# Acoustics_Connections_RP2040.net
KiCad netlist of a schematic drawn in Altium Designer
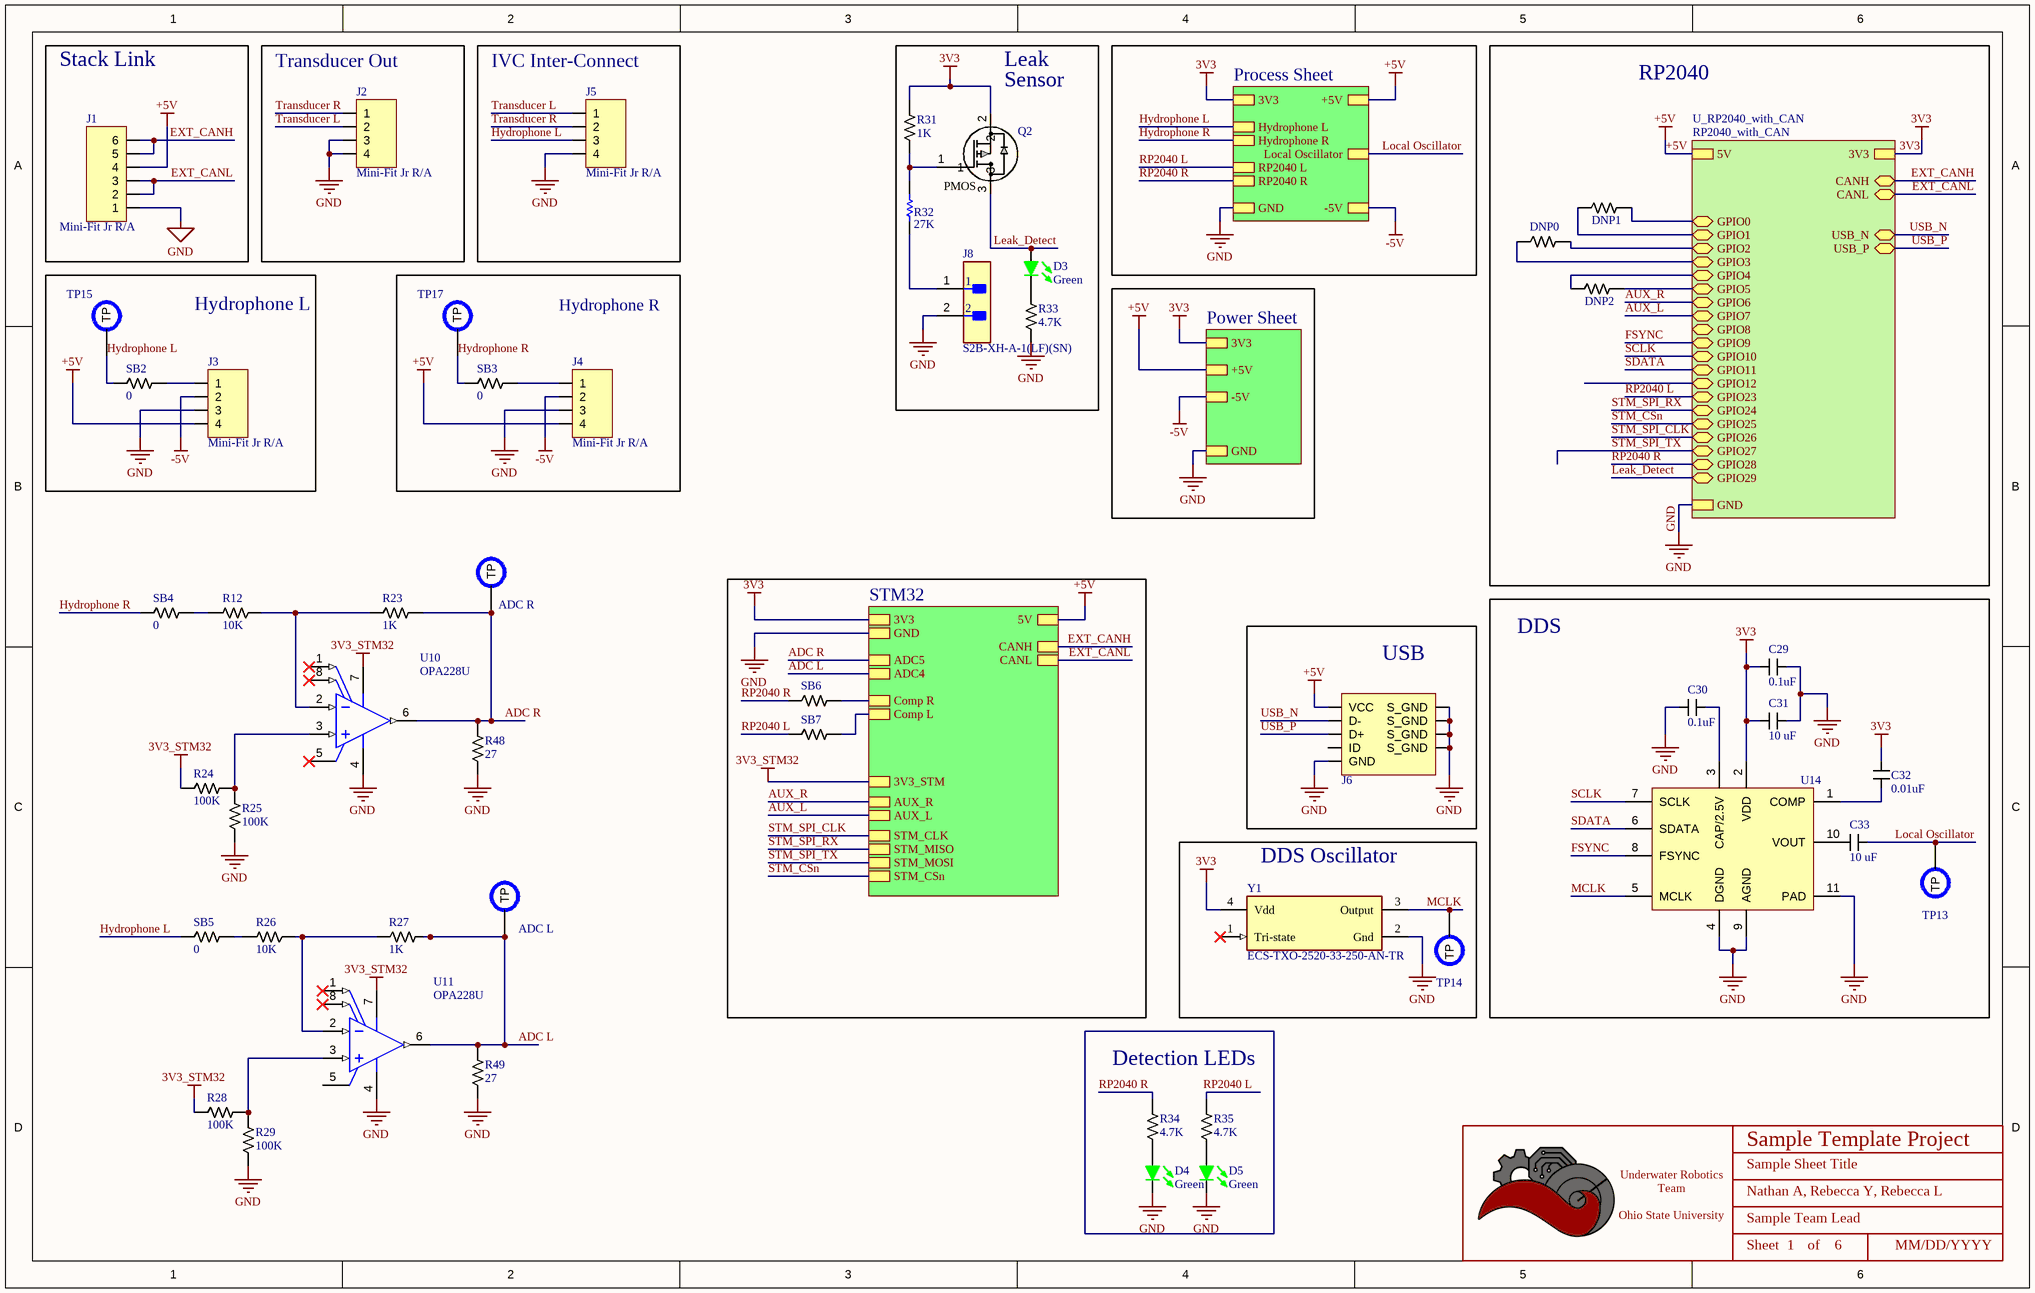
[diagram p0: [Acoustics] Connections & RP2040.SchDoc]

(export (version "E")
  (design (tool "Eeschema 10.0.6"))
  (components
    (comp (ref "ADC L")
      (value "PCB Test Point")
      (footprint "TESTPOINT_1.2MM")
      (fields (field (name "MADE BY") "Robert Pafford"))
      (libsource (lib "Connectors") (part "TESTPOINT"))
    )
    (comp (ref "ADC R")
      (value "PCB Test Point")
      (footprint "TESTPOINT_1.2MM")
      (fields (field (name "MADE BY") "Robert Pafford"))
      (libsource (lib "Connectors") (part "TESTPOINT"))
    )
    (comp (ref "C29")
      (value "0.1uF")
      (footprint "CAPACITOR_0603")
      (description "Cap 100nF 6.3V +/-10%\r\nCeramic 0603")
      (fields
        (field (name "TOLERANCE") "+/- 10%")
        (field (name "VOLTAGE") "6.3V")
        (field (name "MADE BY") "Flip B")
      )
      (libsource (lib "Capacitors") (part "CAPACITOR_0.1uF_0603"))
    )
    (comp (ref "C30")
      (value "0.1uF")
      (footprint "CAPACITOR_0603")
      (description "Cap 100nF 6.3V +/-10%\r\nCeramic 0603")
      (fields
        (field (name "TOLERANCE") "+/- 10%")
        (field (name "VOLTAGE") "6.3V")
        (field (name "MADE BY") "Flip B")
      )
      (libsource (lib "Capacitors") (part "CAPACITOR_0.1uF_0603"))
    )
    (comp (ref "C31")
      (value "10uF Ceramic 6.3V")
      (footprint "CAPACITOR_0603")
      (description "Cap 10uF 6.3V +/-20%\r\nCeramic 0603")
      (fields
        (field (name "TOLERANCE") "+/- 20%")
        (field (name "VOLTAGE") "6.3V")
        (field (name "VALUE (UF)") "10 uF")
        (field (name "MADE BY") "Flip B")
      )
      (libsource (lib "Capacitors") (part "CAPACITOR_10uF_0603"))
    )
    (comp (ref "C32")
      (value "0.01uF")
      (footprint "CAPACITOR_0603")
      (description "10000 pF ±10% 50V Ceramic Capacitor X7R 0603 (1608 Metric)")
      (fields
        (field (name "TOLERANCE") "+/- 10%")
        (field (name "VOLTAGE") "6.3V")
        (field (name "MADE BY") "Flip B")
      )
      (libsource (lib "Capacitors") (part "CAPACITOR_0.01uF_0603_50V"))
    )
    (comp (ref "C33")
      (value "10uF Ceramic 6.3V")
      (footprint "CAPACITOR_0603")
      (description "Cap 10uF 6.3V +/-20%\r\nCeramic 0603")
      (fields
        (field (name "TOLERANCE") "+/- 20%")
        (field (name "VOLTAGE") "6.3V")
        (field (name "VALUE (UF)") "10 uF")
        (field (name "MADE BY") "Flip B")
      )
      (libsource (lib "Capacitors") (part "CAPACITOR_10uF_0603"))
    )
    (comp (ref "D3")
      (value "IN-S63AT5G")
      (footprint "LED_0603")
      (description "LED Green Vf= 3V If = 0.005A\r\nIN-S63AT5G")
      (fields (field (name "COLOR") "Green") (field (name "MADE BY") "Robert Pafford"))
      (libsource (lib "Diodes") (part "LED_Green_0603_3V"))
    )
    (comp (ref "D4")
      (value "IN-S63AT5G")
      (footprint "LED_0603")
      (description "LED Green Vf= 3V If = 0.005A\r\nIN-S63AT5G")
      (fields (field (name "COLOR") "Green") (field (name "MADE BY") "Robert Pafford"))
      (libsource (lib "Diodes") (part "LED_Green_0603_3V"))
    )
    (comp (ref "D5")
      (value "IN-S63AT5G")
      (footprint "LED_0603")
      (description "LED Green Vf= 3V If = 0.005A\r\nIN-S63AT5G")
      (fields (field (name "COLOR") "Green") (field (name "MADE BY") "Robert Pafford"))
      (libsource (lib "Diodes") (part "LED_Green_0603_3V"))
    )
    (comp (ref "DNP0")
      (value "DNP")
      (footprint "RESISTOR_0402")
      (description "Do Not Populate 0402")
      (libsource (lib "Resistors") (part "DNP_0402"))
    )
    (comp (ref "DNP1")
      (value "DNP")
      (footprint "RESISTOR_0402")
      (description "Do Not Populate 0402")
      (libsource (lib "Resistors") (part "DNP_0402"))
    )
    (comp (ref "DNP2")
      (value "DNP")
      (footprint "RESISTOR_0402")
      (description "Do Not Populate 0402")
      (libsource (lib "Resistors") (part "DNP_0402"))
    )
    (comp (ref "J1")
      (value "Mini-Fit Jr R/A")
      (footprint "CONN_MOLEX_MINIFIT JR_6 POS_R/A")
      (description "Molex Minifit Jr. 5569 \r\n6 Pos R/A Natural")
      (fields (field (name "MANUFACTURER") "Molex") (field (name "CREATED BY") "Flip B"))
      (libsource (lib "Connectors") (part "CONN_MOLEX_MINIFIT JR_6POS_R/A"))
    )
    (comp (ref "J2")
      (value "Mini-Fit Jr R/A")
      (footprint "CONN_MOLEX_MINIFIT JR_4 POS_R/A")
      (description "Molex Minifit Jr. 5569 \r\n4 Pos R/A Natural")
      (fields (field (name "MANUFACTURER") "Molex") (field (name "CREATED BY") "Flip B"))
      (libsource (lib "Connectors") (part "CONN_MOLEX_MINIFIT JR_4POS_R/A"))
    )
    (comp (ref "J3")
      (value "Mini-Fit Jr R/A")
      (footprint "CONN_MOLEX_MINIFIT JR_4 POS_R/A")
      (description "Molex Minifit Jr. 5569 \r\n4 Pos R/A Natural")
      (fields (field (name "MANUFACTURER") "Molex") (field (name "CREATED BY") "Flip B"))
      (libsource (lib "Connectors") (part "CONN_MOLEX_MINIFIT JR_4POS_R/A"))
    )
    (comp (ref "J4")
      (value "Mini-Fit Jr R/A")
      (footprint "CONN_MOLEX_MINIFIT JR_4 POS_R/A")
      (description "Molex Minifit Jr. 5569 \r\n4 Pos R/A Natural")
      (fields (field (name "MANUFACTURER") "Molex") (field (name "CREATED BY") "Flip B"))
      (libsource (lib "Connectors") (part "CONN_MOLEX_MINIFIT JR_4POS_R/A"))
    )
    (comp (ref "J5")
      (value "Mini-Fit Jr R/A")
      (footprint "CONN_MOLEX_MINIFIT JR_4 POS_R/A")
      (description "Molex Minifit Jr. 5569 \r\n4 Pos R/A Natural")
      (fields (field (name "MANUFACTURER") "Molex") (field (name "CREATED BY") "Flip B"))
      (libsource (lib "Connectors") (part "CONN_MOLEX_MINIFIT JR_4POS_R/A"))
    )
    (comp (ref "J6")
      (value "USB_MICRO R/A")
      (footprint "CONN_MINIUSB")
      (description "Amphenol Micro USB-B\r\nUSB2.0 5 Pin Right Angle SMD")
      (fields (field (name "MANUFACTURER") "Amphenol") (field (name "CREATED BY") "Flip B"))
      (libsource (lib "Connectors") (part "CONN_MICROUSB"))
    )
    (comp (ref "J8")
      (value "S2B-XH-A-1(LF)(SN)")
      (footprint "FP-S2B-XH-A-1_LF_SN-MFG")
      (description "CONN HEADER R/A 2POS 2.5MM")
      (libsource (lib "Altium Content Vault") (part "3bc925449376181038e59eaffc5286c"))
    )
    (comp (ref "Q2")
      (value "MOSFET P-CHANNEL 20V 4.7A SOT23")
      (footprint "SOT-23-3")
      (description "P-Channel 20 V 4.7A (Tc) 1.56W (Tc) Surface Mount SOT-23")
      (fields
        (field (name "MANUFACTURER_PART_NUMBER") "TSM500P02CX")
        (field (name "CREATED BY") "Robert Pafford")
      )
      (libsource (lib "Transistors") (part "TSM500P02CX"))
    )
    (comp (ref "R12")
      (value "10k Ohm 5% 1/10W")
      (footprint "RESISTOR_0603")
      (description "RES 10k OHM 5% 1/10W 0603")
      (fields
        (field (name "TOLERANCE") "+/- 5%")
        (field (name "VALUE  (OHMS)") "10K")
        (field (name "MADE BY") "Robert Pafford")
      )
      (libsource (lib "Resistors") (part "RESISTOR_10K_0603"))
    )
    (comp (ref "R23")
      (value "1k Ohm 5% 1/8W")
      (footprint "RESISTOR_0603")
      (description "RES 1k OHM 5% 1/8W 0603")
      (fields
        (field (name "TOLERANCE") "+/- 5%")
        (field (name "VALUE  (OHMS)") "1K")
        (field (name "MADE BY") "Robert Pafford")
      )
      (libsource (lib "Resistors") (part "RESISTOR_1K_0603"))
    )
    (comp (ref "R24")
      (value "100k Ohm 5% 1/8W")
      (footprint "RESISTOR_0603")
      (description "RES 100k OHM 5% 1/10W 0603")
      (fields
        (field (name "TOLERANCE") "+/- 5%")
        (field (name "VALUE  (OHMS)") "100K")
        (field (name "MADE BY") "Flip B")
      )
      (libsource (lib "Resistors") (part "RESISTOR_100K_0603"))
    )
    (comp (ref "R25")
      (value "100k Ohm 5% 1/8W")
      (footprint "RESISTOR_0603")
      (description "RES 100k OHM 5% 1/10W 0603")
      (fields
        (field (name "TOLERANCE") "+/- 5%")
        (field (name "VALUE  (OHMS)") "100K")
        (field (name "MADE BY") "Flip B")
      )
      (libsource (lib "Resistors") (part "RESISTOR_100K_0603"))
    )
    (comp (ref "R26")
      (value "10k Ohm 5% 1/10W")
      (footprint "RESISTOR_0603")
      (description "RES 10k OHM 5% 1/10W 0603")
      (fields
        (field (name "TOLERANCE") "+/- 5%")
        (field (name "VALUE  (OHMS)") "10K")
        (field (name "MADE BY") "Robert Pafford")
      )
      (libsource (lib "Resistors") (part "RESISTOR_10K_0603"))
    )
    (comp (ref "R27")
      (value "1k Ohm 5% 1/8W")
      (footprint "RESISTOR_0603")
      (description "RES 1k OHM 5% 1/8W 0603")
      (fields
        (field (name "TOLERANCE") "+/- 5%")
        (field (name "VALUE  (OHMS)") "1K")
        (field (name "MADE BY") "Robert Pafford")
      )
      (libsource (lib "Resistors") (part "RESISTOR_1K_0603"))
    )
    (comp (ref "R28")
      (value "100k Ohm 5% 1/8W")
      (footprint "RESISTOR_0603")
      (description "RES 100k OHM 5% 1/10W 0603")
      (fields
        (field (name "TOLERANCE") "+/- 5%")
        (field (name "VALUE  (OHMS)") "100K")
        (field (name "MADE BY") "Flip B")
      )
      (libsource (lib "Resistors") (part "RESISTOR_100K_0603"))
    )
    (comp (ref "R29")
      (value "100k Ohm 5% 1/8W")
      (footprint "RESISTOR_0603")
      (description "RES 100k OHM 5% 1/10W 0603")
      (fields
        (field (name "TOLERANCE") "+/- 5%")
        (field (name "VALUE  (OHMS)") "100K")
        (field (name "MADE BY") "Flip B")
      )
      (libsource (lib "Resistors") (part "RESISTOR_100K_0603"))
    )
    (comp (ref "R31")
      (value "1k Ohm 1% 1/16W")
      (footprint "RESISTOR_0402")
      (description "RES 1k OHM 1% 1/16W 0402")
      (fields
        (field (name "TOLERANCE") "+/- 1%")
        (field (name "VALUE  (OHMS)") "1K")
        (field (name "MADE BY") "Robert Pafford")
      )
      (libsource (lib "Resistors") (part "RESISTOR_1K_0402"))
    )
    (comp (ref "R32")
      (value "27K")
      (footprint "RESC1005X40X25ML05T05")
      (description "RES SMD 27K OHM 5% 1/10W 0402ERJ-2GEJ273X")
      (fields (field (name "MANUFACTURER") "Panasonic") (field (name "PART NUMBER") "ERJ-2GEJ273X"))
      (libsource (lib "Altium Content Vault") (part "RES"))
    )
    (comp (ref "R33")
      (value "4.7k Ohm 5% 1/10W")
      (footprint "RESISTOR_0603")
      (description "RES 4.7k OHM 5% 1/10W 0603")
      (fields
        (field (name "TOLERANCE") "+/- 5%")
        (field (name "VALUE  (OHMS)") "4.7K")
        (field (name "MADE BY") "Robert Pafford")
      )
      (libsource (lib "Resistors") (part "RESISTOR_4.7K_0603"))
    )
    (comp (ref "R34")
      (value "4.7k Ohm 5% 1/10W")
      (footprint "RESISTOR_0603")
      (description "RES 4.7k OHM 5% 1/10W 0603")
      (fields
        (field (name "TOLERANCE") "+/- 5%")
        (field (name "VALUE  (OHMS)") "4.7K")
        (field (name "MADE BY") "Robert Pafford")
      )
      (libsource (lib "Resistors") (part "RESISTOR_4.7K_0603"))
    )
    (comp (ref "R35")
      (value "4.7k Ohm 5% 1/10W")
      (footprint "RESISTOR_0603")
      (description "RES 4.7k OHM 5% 1/10W 0603")
      (fields
        (field (name "TOLERANCE") "+/- 5%")
        (field (name "VALUE  (OHMS)") "4.7K")
        (field (name "MADE BY") "Robert Pafford")
      )
      (libsource (lib "Resistors") (part "RESISTOR_4.7K_0603"))
    )
    (comp (ref "R48")
      (value "27 Ohm 5% 1/8W")
      (footprint "RESISTOR_0603")
      (description "RES 27 OHM 5% 1/8W 0603")
      (fields
        (field (name "TOLERANCE") "+/- 5%")
        (field (name "VALUE  (OHMS)") "27")
        (field (name "MADE BY") "Robert Pafford")
      )
      (libsource (lib "Resistors") (part "RESISTOR_27_0603"))
    )
    (comp (ref "R49")
      (value "27 Ohm 5% 1/8W")
      (footprint "RESISTOR_0603")
      (description "RES 27 OHM 5% 1/8W 0603")
      (fields
        (field (name "TOLERANCE") "+/- 5%")
        (field (name "VALUE  (OHMS)") "27")
        (field (name "MADE BY") "Robert Pafford")
      )
      (libsource (lib "Resistors") (part "RESISTOR_27_0603"))
    )
    (comp (ref "SB2")
      (value "0 Ohm Jumper No Fit")
      (footprint "RESISTOR_0603")
      (description "0 Ohm Jumper No Fit for Solder Bridge")
      (fields (field (name "VALUE  (OHMS)") "0") (field (name "MADE BY") "Robert Pafford"))
      (libsource (lib "Resistors") (part "JUMPER_0_0603"))
    )
    (comp (ref "SB3")
      (value "0 Ohm Jumper No Fit")
      (footprint "RESISTOR_0603")
      (description "0 Ohm Jumper No Fit for Solder Bridge")
      (fields (field (name "VALUE  (OHMS)") "0") (field (name "MADE BY") "Robert Pafford"))
      (libsource (lib "Resistors") (part "JUMPER_0_0603"))
    )
    (comp (ref "SB4")
      (value "0 Ohm Jumper No Fit")
      (footprint "RESISTOR_0603")
      (description "0 Ohm Jumper No Fit for Solder Bridge")
      (fields (field (name "VALUE  (OHMS)") "0") (field (name "MADE BY") "Robert Pafford"))
      (libsource (lib "Resistors") (part "JUMPER_0_0603"))
    )
    (comp (ref "SB5")
      (value "0 Ohm Jumper No Fit")
      (footprint "RESISTOR_0603")
      (description "0 Ohm Jumper No Fit for Solder Bridge")
      (fields (field (name "VALUE  (OHMS)") "0") (field (name "MADE BY") "Robert Pafford"))
      (libsource (lib "Resistors") (part "JUMPER_0_0603"))
    )
    (comp (ref "SB6")
      (value "0 Ohm Jumper No Fit")
      (footprint "RESISTOR_0603")
      (description "0 Ohm Jumper No Fit for Solder Bridge")
      (fields (field (name "MADE BY") "Robert Pafford"))
      (libsource (lib "Resistors") (part "JUMPER_0_0603"))
    )
    (comp (ref "SB7")
      (value "0 Ohm Jumper No Fit")
      (footprint "RESISTOR_0603")
      (description "0 Ohm Jumper No Fit for Solder Bridge")
      (fields (field (name "MADE BY") "Robert Pafford"))
      (libsource (lib "Resistors") (part "JUMPER_0_0603"))
    )
    (comp (ref "TP13")
      (value "PCB Test Point")
      (footprint "TESTPOINT_1.2MM")
      (fields (field (name "MADE BY") "Robert Pafford"))
      (libsource (lib "Connectors") (part "TESTPOINT"))
    )
    (comp (ref "TP14")
      (value "PCB Test Point")
      (footprint "TESTPOINT_1.2MM")
      (fields (field (name "MADE BY") "Robert Pafford"))
      (libsource (lib "Connectors") (part "TESTPOINT"))
    )
    (comp (ref "TP15")
      (value "PCB Test Point")
      (footprint "TESTPOINT_1.2MM")
      (fields (field (name "MADE BY") "Robert Pafford"))
      (libsource (lib "Connectors") (part "TESTPOINT"))
    )
    (comp (ref "TP17")
      (value "PCB Test Point")
      (footprint "TESTPOINT_1.2MM")
      (fields (field (name "MADE BY") "Robert Pafford"))
      (libsource (lib "Connectors") (part "TESTPOINT"))
    )
    (comp (ref "U10")
      (value "OPA228U")
      (footprint "D0008A_M")
      (fields (field (name "MANUFACTURER") "Texas Instruments"))
      (libsource (lib "Altium Content Vault") (part "TI-OPA228-X8"))
    )
    (comp (ref "U11")
      (value "OPA228U")
      (footprint "D0008A_M")
      (fields (field (name "MANUFACTURER") "Texas Instruments"))
      (libsource (lib "Altium Content Vault") (part "TI-OPA228-X8"))
    )
    (comp (ref "U14")
      (value "IC DDS 5MHZ 10BIT 10LFCSP")
      (footprint "CP-10-9")
      (description "Direct Digital Synthesis IC 10 b 5 MHz 28 b Tuning 10-LFCSP-WD (3x3)")
      (libsource (lib "Integrated Circuits") (part "AD9837ACPZ"))
    )
    (comp (ref "Y1")
      (value "ECS-TXO-2520-33-250-AN-TR")
      (footprint "FP-ECS-TXO-2520-MFG")
      (description "XTAL OSC TCXO 25.0000MHZ HCMOS")
      (libsource (lib "Altium Content Vault") (part "04cd953f3cf158082f8c09fbdb924ef"))
    )
  )
  (nets
    (net (code "1") (name "+5V") (class "Default")
      (node (ref "J1") (pin "4") (pinfunction "4_4") (pintype "passive"))
      (node (ref "J3") (pin "4") (pinfunction "4_4") (pintype "passive"))
      (node (ref "J4") (pin "4") (pinfunction "4_4") (pintype "passive"))
      (node (ref "J6") (pin "1") (pinfunction "VCC_1") (pintype "passive"))
    )
    (net (code "2") (name "-5V") (class "Default")
      (node (ref "J3") (pin "2") (pinfunction "2_2") (pintype "passive"))
      (node (ref "J4") (pin "2") (pinfunction "2_2") (pintype "passive"))
    )
    (net (code "3") (name "/ADC L") (class "Default")
      (node (ref "ADC L") (pin "TP") (pinfunction "TP_TP") (pintype "passive"))
      (node (ref "R27") (pin "1") (pinfunction "1_1") (pintype "passive"))
      (node (ref "R49") (pin "1") (pinfunction "1_1") (pintype "passive"))
      (node (ref "U11") (pin "6") (pinfunction "OUT_6") (pintype "output"))
    )
    (net (code "4") (name "/ADC R") (class "Default")
      (node (ref "ADC R") (pin "TP") (pinfunction "TP_TP") (pintype "passive"))
      (node (ref "R23") (pin "1") (pinfunction "1_1") (pintype "passive"))
      (node (ref "R48") (pin "1") (pinfunction "1_1") (pintype "passive"))
      (node (ref "U10") (pin "6") (pinfunction "OUT_6") (pintype "output"))
    )
    (net (code "7") (name "/Comp L") (class "Default")
      (node (ref "SB7") (pin "1") (pinfunction "1_1") (pintype "passive"))
    )
    (net (code "8") (name "/Comp R") (class "Default")
      (node (ref "SB6") (pin "1") (pinfunction "1_1") (pintype "passive"))
    )
    (net (code "9") (name "/EXT_CANH") (class "Default")
      (node (ref "J1") (pin "5") (pinfunction "5_5") (pintype "passive"))
      (node (ref "J1") (pin "6") (pinfunction "6_6") (pintype "passive"))
    )
    (net (code "10") (name "/EXT_CANL") (class "Default")
      (node (ref "J1") (pin "2") (pinfunction "2_2") (pintype "passive"))
      (node (ref "J1") (pin "3") (pinfunction "3_3") (pintype "passive"))
    )
    (net (code "11") (name "/FSYNC") (class "Default")
      (node (ref "U14") (pin "8") (pinfunction "FSYNC_8") (pintype "passive"))
    )
    (net (code "12") (name "/GPIO0") (class "Default")
      (node (ref "DNP1") (pin "1") (pinfunction "1_1") (pintype "passive"))
    )
    (net (code "13") (name "/GPIO1") (class "Default")
      (node (ref "DNP1") (pin "2") (pinfunction "2_2") (pintype "passive"))
    )
    (net (code "14") (name "/GPIO2") (class "Default")
      (node (ref "DNP0") (pin "1") (pinfunction "1_1") (pintype "passive"))
    )
    (net (code "15") (name "/GPIO3") (class "Default")
      (node (ref "DNP0") (pin "2") (pinfunction "2_2") (pintype "passive"))
    )
    (net (code "16") (name "/GPIO4") (class "Default")
      (node (ref "DNP2") (pin "2") (pinfunction "2_2") (pintype "passive"))
    )
    (net (code "17") (name "/GPIO5") (class "Default")
      (node (ref "DNP2") (pin "1") (pinfunction "1_1") (pintype "passive"))
    )
    (net (code "20") (name "/Hydrophone L") (class "Default")
      (node (ref "J5") (pin "3") (pinfunction "3_3") (pintype "passive"))
      (node (ref "SB2") (pin "2") (pinfunction "2_2") (pintype "passive"))
      (node (ref "SB5") (pin "2") (pinfunction "2_2") (pintype "passive"))
      (node (ref "TP15") (pin "TP") (pinfunction "TP_TP") (pintype "passive"))
    )
    (net (code "21") (name "/Hydrophone R") (class "Default")
      (node (ref "SB3") (pin "2") (pinfunction "2_2") (pintype "passive"))
      (node (ref "SB4") (pin "2") (pinfunction "2_2") (pintype "passive"))
      (node (ref "TP17") (pin "TP") (pinfunction "TP_TP") (pintype "passive"))
    )
    (net (code "22") (name "/Leak_Detect") (class "Default")
      (node (ref "D3") (pin "1") (pinfunction "1_1") (pintype "passive"))
      (node (ref "Q2") (pin "3") (pinfunction "3_3") (pintype "passive"))
    )
    (net (code "23") (name "/Local Oscillator") (class "Default")
      (node (ref "C33") (pin "2") (pinfunction "2_2") (pintype "passive"))
      (node (ref "TP13") (pin "TP") (pinfunction "TP_TP") (pintype "passive"))
    )
    (net (code "24") (name "/MCLK") (class "Default")
      (node (ref "TP14") (pin "TP") (pinfunction "TP_TP") (pintype "passive"))
      (node (ref "U14") (pin "5") (pinfunction "MCLK_5") (pintype "passive"))
      (node (ref "Y1") (pin "3") (pinfunction "Output_3") (pintype "tri_state"))
    )
    (net (code "25") (name "/RP2040 L") (class "Default")
      (node (ref "R35") (pin "1") (pinfunction "1_1") (pintype "passive"))
      (node (ref "SB7") (pin "2") (pinfunction "2_2") (pintype "passive"))
    )
    (net (code "26") (name "/RP2040 R") (class "Default")
      (node (ref "R34") (pin "1") (pinfunction "1_1") (pintype "passive"))
      (node (ref "SB6") (pin "2") (pinfunction "2_2") (pintype "passive"))
    )
    (net (code "27") (name "/SCLK") (class "Default")
      (node (ref "U14") (pin "7") (pinfunction "SCLK_7") (pintype "passive"))
    )
    (net (code "28") (name "/SDATA") (class "Default")
      (node (ref "U14") (pin "6") (pinfunction "SDATA_6") (pintype "passive"))
    )
    (net (code "33") (name "/Transducer L") (class "Default")
      (node (ref "J2") (pin "2") (pinfunction "2_2") (pintype "passive"))
      (node (ref "J5") (pin "1") (pinfunction "1_1") (pintype "passive"))
    )
    (net (code "34") (name "/Transducer R") (class "Default")
      (node (ref "J2") (pin "1") (pinfunction "1_1") (pintype "passive"))
      (node (ref "J5") (pin "2") (pinfunction "2_2") (pintype "passive"))
    )
    (net (code "35") (name "/USB_N") (class "Default")
      (node (ref "J6") (pin "2") (pinfunction "D-_2") (pintype "passive"))
    )
    (net (code "36") (name "/USB_P") (class "Default")
      (node (ref "J6") (pin "3") (pinfunction "D+_3") (pintype "passive"))
    )
    (net (code "37") (name "3V3") (class "Default")
      (node (ref "C29") (pin "2") (pinfunction "2_2") (pintype "passive"))
      (node (ref "C31") (pin "1") (pinfunction "1_1") (pintype "passive"))
      (node (ref "C32") (pin "1") (pinfunction "1_1") (pintype "passive"))
      (node (ref "Q2") (pin "2") (pinfunction "2_2") (pintype "passive"))
      (node (ref "R31") (pin "1") (pinfunction "1_1") (pintype "passive"))
      (node (ref "U14") (pin "2") (pinfunction "VDD_2") (pintype "passive"))
      (node (ref "Y1") (pin "4") (pinfunction "Vdd_4") (pintype "power_in"))
    )
    (net (code "38") (name "3V3_STM32") (class "Default")
      (node (ref "R24") (pin "2") (pinfunction "2_2") (pintype "passive"))
      (node (ref "R28") (pin "2") (pinfunction "2_2") (pintype "passive"))
      (node (ref "U10") (pin "7") (pinfunction "V+_7") (pintype "power_in"))
      (node (ref "U11") (pin "7") (pinfunction "V+_7") (pintype "power_in"))
    )
    (net (code "39") (name "GND") (class "Default")
      (node (ref "C29") (pin "1") (pinfunction "1_1") (pintype "passive"))
      (node (ref "C30") (pin "1") (pinfunction "1_1") (pintype "passive"))
      (node (ref "C31") (pin "2") (pinfunction "2_2") (pintype "passive"))
      (node (ref "D4") (pin "2") (pinfunction "2_2") (pintype "passive"))
      (node (ref "D5") (pin "2") (pinfunction "2_2") (pintype "passive"))
      (node (ref "J1") (pin "1") (pinfunction "1_1") (pintype "passive"))
      (node (ref "J2") (pin "3") (pinfunction "3_3") (pintype "passive"))
      (node (ref "J2") (pin "4") (pinfunction "4_4") (pintype "passive"))
      (node (ref "J3") (pin "3") (pinfunction "3_3") (pintype "passive"))
      (node (ref "J4") (pin "3") (pinfunction "3_3") (pintype "passive"))
      (node (ref "J5") (pin "4") (pinfunction "4_4") (pintype "passive"))
      (node (ref "J6") (pin "5") (pinfunction "GND_5") (pintype "passive"))
      (node (ref "J6") (pin "6") (pinfunction "S_GND_6") (pintype "passive"))
      (node (ref "J6") (pin "7") (pinfunction "S_GND_7") (pintype "passive"))
      (node (ref "J6") (pin "8") (pinfunction "S_GND_8") (pintype "passive"))
      (node (ref "J6") (pin "9") (pinfunction "S_GND_9") (pintype "passive"))
      (node (ref "J8") (pin "2") (pinfunction "2_2") (pintype "passive"))
      (node (ref "R25") (pin "2") (pinfunction "2_2") (pintype "passive"))
      (node (ref "R29") (pin "2") (pinfunction "2_2") (pintype "passive"))
      (node (ref "R33") (pin "2") (pinfunction "2_2") (pintype "passive"))
      (node (ref "R48") (pin "2") (pinfunction "2_2") (pintype "passive"))
      (node (ref "R49") (pin "2") (pinfunction "2_2") (pintype "passive"))
      (node (ref "U10") (pin "4") (pinfunction "V-_4") (pintype "power_in"))
      (node (ref "U11") (pin "4") (pinfunction "V-_4") (pintype "power_in"))
      (node (ref "U14") (pin "11") (pinfunction "PAD_11") (pintype "passive"))
      (node (ref "U14") (pin "4") (pinfunction "DGND_4") (pintype "passive"))
      (node (ref "U14") (pin "9") (pinfunction "AGND_9") (pintype "passive"))
      (node (ref "Y1") (pin "2") (pinfunction "Gnd_2") (pintype "power_in"))
    )
    (net (code "40") (name "Net-(D3-Pad2)") (class "Default")
      (node (ref "D3") (pin "2") (pinfunction "2_2") (pintype "passive"))
      (node (ref "R33") (pin "1") (pinfunction "1_1") (pintype "passive"))
    )
    (net (code "41") (name "Net-(D4-Pad1)") (class "Default")
      (node (ref "D4") (pin "1") (pinfunction "1_1") (pintype "passive"))
      (node (ref "R34") (pin "2") (pinfunction "2_2") (pintype "passive"))
    )
    (net (code "42") (name "Net-(D5-Pad1)") (class "Default")
      (node (ref "D5") (pin "1") (pinfunction "1_1") (pintype "passive"))
      (node (ref "R35") (pin "2") (pinfunction "2_2") (pintype "passive"))
    )
    (net (code "43") (name "Net-(J3-Pad1)") (class "Default")
      (node (ref "J3") (pin "1") (pinfunction "1_1") (pintype "passive"))
      (node (ref "SB2") (pin "1") (pinfunction "1_1") (pintype "passive"))
    )
    (net (code "44") (name "Net-(J4-Pad1)") (class "Default")
      (node (ref "J4") (pin "1") (pinfunction "1_1") (pintype "passive"))
      (node (ref "SB3") (pin "1") (pinfunction "1_1") (pintype "passive"))
    )
    (net (code "45") (name "Net-(J8-Pad1)") (class "Default")
      (node (ref "J8") (pin "1") (pinfunction "1_1") (pintype "passive"))
      (node (ref "R32") (pin "1") (pinfunction "1_1") (pintype "passive"))
    )
    (net (code "46") (name "Net-(Q2-Pad1)") (class "Default")
      (node (ref "Q2") (pin "1") (pinfunction "1_1") (pintype "passive"))
      (node (ref "R31") (pin "2") (pinfunction "2_2") (pintype "passive"))
      (node (ref "R32") (pin "2") (pinfunction "2_2") (pintype "passive"))
    )
    (net (code "47") (name "Net-(R12-Pad1)") (class "Default")
      (node (ref "R12") (pin "1") (pinfunction "1_1") (pintype "passive"))
      (node (ref "SB4") (pin "1") (pinfunction "1_1") (pintype "passive"))
    )
    (net (code "48") (name "Net-(R26-Pad1)") (class "Default")
      (node (ref "R26") (pin "1") (pinfunction "1_1") (pintype "passive"))
      (node (ref "SB5") (pin "1") (pinfunction "1_1") (pintype "passive"))
    )
    (net (code "49") (name "Net-(U10-IN+)") (class "Default")
      (node (ref "R24") (pin "1") (pinfunction "1_1") (pintype "passive"))
      (node (ref "R25") (pin "1") (pinfunction "1_1") (pintype "passive"))
      (node (ref "U10") (pin "3") (pinfunction "IN+_3") (pintype "input"))
    )
    (net (code "50") (name "Net-(U10-IN-)") (class "Default")
      (node (ref "R12") (pin "2") (pinfunction "2_2") (pintype "passive"))
      (node (ref "R23") (pin "2") (pinfunction "2_2") (pintype "passive"))
      (node (ref "U10") (pin "2") (pinfunction "IN-_2") (pintype "input"))
    )
    (net (code "51") (name "Net-(U11-IN+)") (class "Default")
      (node (ref "R28") (pin "1") (pinfunction "1_1") (pintype "passive"))
      (node (ref "R29") (pin "1") (pinfunction "1_1") (pintype "passive"))
      (node (ref "U11") (pin "3") (pinfunction "IN+_3") (pintype "input"))
    )
    (net (code "52") (name "Net-(U11-IN-)") (class "Default")
      (node (ref "R26") (pin "2") (pinfunction "2_2") (pintype "passive"))
      (node (ref "R27") (pin "2") (pinfunction "2_2") (pintype "passive"))
      (node (ref "U11") (pin "2") (pinfunction "IN-_2") (pintype "input"))
    )
    (net (code "53") (name "Net-(U14-CAP{slash}2.5V)") (class "Default")
      (node (ref "C30") (pin "2") (pinfunction "2_2") (pintype "passive"))
      (node (ref "U14") (pin "3") (pinfunction "CAP/2.5V_3") (pintype "passive"))
    )
    (net (code "54") (name "Net-(U14-COMP)") (class "Default")
      (node (ref "C32") (pin "2") (pinfunction "2_2") (pintype "passive"))
      (node (ref "U14") (pin "1") (pinfunction "COMP_1") (pintype "passive"))
    )
    (net (code "55") (name "Net-(U14-VOUT)") (class "Default")
      (node (ref "C33") (pin "1") (pinfunction "1_1") (pintype "passive"))
      (node (ref "U14") (pin "10") (pinfunction "VOUT_10") (pintype "passive"))
    )
    (net (code "56") (name "unconnected-(J6-ID-Pad4)") (class "Default")
      (node (ref "J6") (pin "4") (pinfunction "ID_4") (pintype "passive"))
    )
    (net (code "57") (name "unconnected-(U10-NC-Pad5)") (class "Default")
      (node (ref "U10") (pin "5") (pinfunction "NC_5") (pintype "passive+no_connect"))
    )
    (net (code "58") (name "unconnected-(U10-TRIM-Pad1)") (class "Default")
      (node (ref "U10") (pin "1") (pinfunction "TRIM_1") (pintype "input+no_connect"))
    )
    (net (code "59") (name "unconnected-(U10-TRIM-Pad8)") (class "Default")
      (node (ref "U10") (pin "8") (pinfunction "TRIM_8") (pintype "input+no_connect"))
    )
    (net (code "60") (name "unconnected-(U11-NC-Pad5)") (class "Default")
      (node (ref "U11") (pin "5") (pinfunction "NC_5") (pintype "passive"))
    )
    (net (code "61") (name "unconnected-(U11-TRIM-Pad1)") (class "Default")
      (node (ref "U11") (pin "1") (pinfunction "TRIM_1") (pintype "input+no_connect"))
    )
    (net (code "62") (name "unconnected-(U11-TRIM-Pad8)") (class "Default")
      (node (ref "U11") (pin "8") (pinfunction "TRIM_8") (pintype "input+no_connect"))
    )
    (net (code "63") (name "unconnected-(Y1-Tri-state-Pad1)") (class "Default")
      (node (ref "Y1") (pin "1") (pinfunction "Tri-state_1") (pintype "input+no_connect"))
    )
  )
)
